# FingerPrint_Device_PCB.net
KiCad netlist of a schematic drawn in Altium Designer
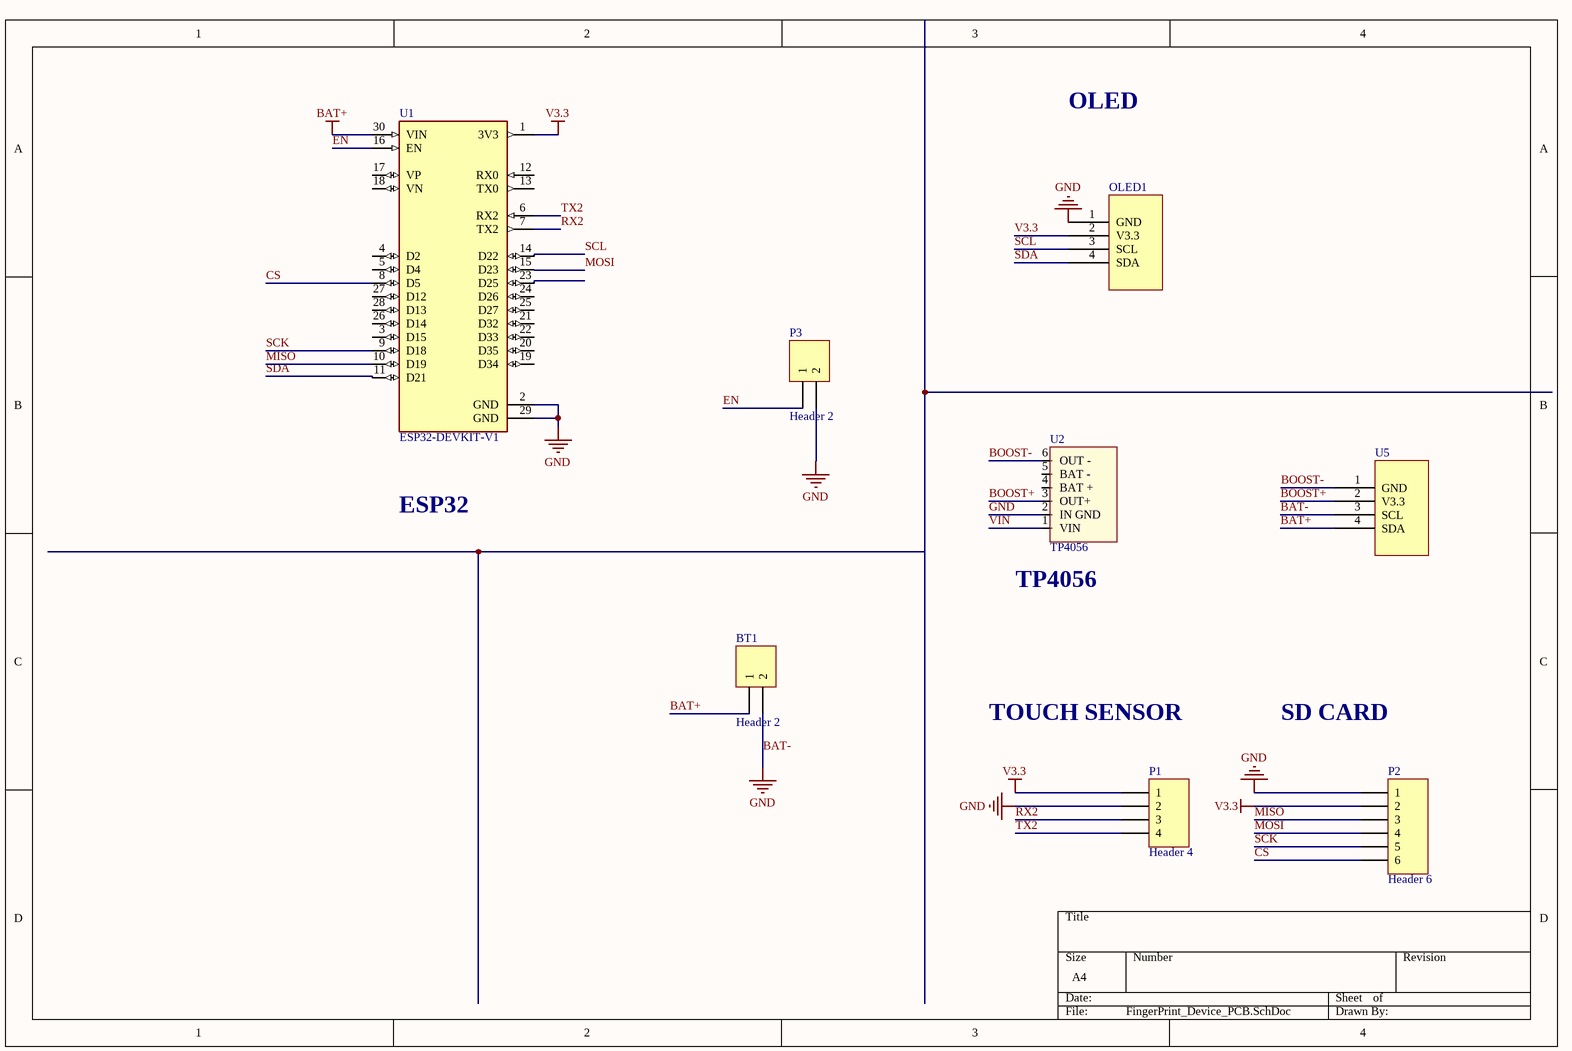
[diagram p0: FingerPrint_Device_PCB.SchDoc]

(export (version "E")
  (design (tool "Eeschema 10.0.6"))
  (components
    (comp (ref "BT1")
      (value "Header 2")
      (footprint "HDR1X2")
      (description "Header, 2-Pin")
      (fields (field (name "PUBLISHER") "Altium Limited"))
      (libsource (lib "Miscellaneous Connectors") (part "Header 2"))
    )
    (comp (ref "OLED1") (value "OLED") (footprint "OLED") (libsource (lib "OLED") (part "OLED")))
    (comp (ref "P1")
      (value "Header 4")
      (footprint "HDR1X4")
      (description "Header, 4-Pin")
      (fields (field (name "PUBLISHER") "Altium Limited"))
      (libsource (lib "Miscellaneous Connectors") (part "Header 4"))
    )
    (comp (ref "P2")
      (value "Header 6")
      (footprint "HDR1X6")
      (description "Header, 6-Pin")
      (fields (field (name "PUBLISHER") "Altium Limited"))
      (libsource (lib "Miscellaneous Connectors") (part "Header 6"))
    )
    (comp (ref "P3")
      (value "Header 2")
      (footprint "HDR1X2")
      (description "Header, 2-Pin")
      (fields (field (name "PUBLISHER") "Altium Limited"))
      (libsource (lib "Miscellaneous Connectors") (part "Header 2"))
    )
    (comp (ref "U1")
      (value "ESP32-DEVKIT-V1")
      (footprint "MODULE_ESP32_DEVKIT_V1")
      (fields (field (name "MF") "Do it"))
      (libsource (lib "ESP32-DEVKIT-V1") (part "ESP32-DEVKIT-V1"))
    )
    (comp (ref "U2")
      (value "TP4056")
      (footprint "tp4056")
      (description "Dushan")
      (libsource (lib "TP4056") (part "TP4056"))
    )
    (comp (ref "U5") (value "OLED") (footprint "MT3608") (libsource (lib "OLED") (part "OLED")))
  )
  (nets
    (net (code "1") (name "/BOOST+") (class "Default")
      (node (ref "U2") (pin "3") (pinfunction "OUT+_3") (pintype "passive"))
      (node (ref "U5") (pin "2") (pinfunction "V3.3_2") (pintype "passive"))
    )
    (net (code "2") (name "/BOOST-") (class "Default")
      (node (ref "U2") (pin "6") (pinfunction "OUT_-_6") (pintype "passive"))
      (node (ref "U5") (pin "1") (pinfunction "GND_1") (pintype "passive"))
    )
    (net (code "3") (name "/CS") (class "Default")
      (node (ref "P2") (pin "6") (pinfunction "6_6") (pintype "passive"))
      (node (ref "U1") (pin "8") (pinfunction "D5_8") (pintype "bidirectional"))
    )
    (net (code "4") (name "/EN") (class "Default")
      (node (ref "P3") (pin "1") (pinfunction "1_1") (pintype "passive"))
      (node (ref "U1") (pin "16") (pinfunction "EN_16") (pintype "input"))
    )
    (net (code "5") (name "/MISO") (class "Default")
      (node (ref "P2") (pin "3") (pinfunction "3_3") (pintype "passive"))
      (node (ref "U1") (pin "10") (pinfunction "D19_10") (pintype "bidirectional"))
    )
    (net (code "6") (name "/MOSI") (class "Default")
      (node (ref "P2") (pin "4") (pinfunction "4_4") (pintype "passive"))
      (node (ref "U1") (pin "15") (pinfunction "D23_15") (pintype "bidirectional"))
    )
    (net (code "7") (name "/RX2") (class "Default")
      (node (ref "P1") (pin "3") (pinfunction "3_3") (pintype "passive"))
      (node (ref "U1") (pin "7") (pinfunction "TX2_7") (pintype "output"))
    )
    (net (code "8") (name "/SCK") (class "Default")
      (node (ref "P2") (pin "5") (pinfunction "5_5") (pintype "passive"))
      (node (ref "U1") (pin "9") (pinfunction "D18_9") (pintype "bidirectional"))
    )
    (net (code "9") (name "/SCL") (class "Default")
      (node (ref "OLED1") (pin "3") (pinfunction "SCL_3") (pintype "passive"))
      (node (ref "U1") (pin "14") (pinfunction "D22_14") (pintype "bidirectional"))
    )
    (net (code "10") (name "/SDA") (class "Default")
      (node (ref "OLED1") (pin "4") (pinfunction "SDA_4") (pintype "passive"))
      (node (ref "U1") (pin "11") (pinfunction "D21_11") (pintype "bidirectional"))
    )
    (net (code "11") (name "/TX2") (class "Default")
      (node (ref "P1") (pin "4") (pinfunction "4_4") (pintype "passive"))
      (node (ref "U1") (pin "6") (pinfunction "RX2_6") (pintype "input"))
    )
    (net (code "12") (name "/VIN") (class "Default")
      (node (ref "U2") (pin "1") (pinfunction "VIN_1") (pintype "passive"))
    )
    (net (code "13") (name "BAT+") (class "Default")
      (node (ref "BT1") (pin "1") (pinfunction "1_1") (pintype "passive"))
      (node (ref "U1") (pin "30") (pinfunction "VIN_30") (pintype "input"))
      (node (ref "U5") (pin "4") (pinfunction "SDA_4") (pintype "passive"))
    )
    (net (code "14") (name "GND") (class "Default")
      (node (ref "BT1") (pin "2") (pinfunction "2_2") (pintype "passive"))
      (node (ref "OLED1") (pin "1") (pinfunction "GND_1") (pintype "passive"))
      (node (ref "P1") (pin "2") (pinfunction "2_2") (pintype "passive"))
      (node (ref "P2") (pin "1") (pinfunction "1_1") (pintype "passive"))
      (node (ref "P3") (pin "2") (pinfunction "2_2") (pintype "passive"))
      (node (ref "U1") (pin "2") (pinfunction "GND_2") (pintype "power_in"))
      (node (ref "U1") (pin "29") (pinfunction "GND_29") (pintype "power_in"))
      (node (ref "U2") (pin "2") (pinfunction "IN_GND_2") (pintype "passive"))
      (node (ref "U5") (pin "3") (pinfunction "SCL_3") (pintype "passive"))
    )
    (net (code "15") (name "V3.3") (class "Default")
      (node (ref "OLED1") (pin "2") (pinfunction "V3.3_2") (pintype "passive"))
      (node (ref "P1") (pin "1") (pinfunction "1_1") (pintype "passive"))
      (node (ref "P2") (pin "2") (pinfunction "2_2") (pintype "passive"))
      (node (ref "U1") (pin "1") (pinfunction "3V3_1") (pintype "output"))
    )
    (net (code "16") (name "unconnected-(U1-D2-Pad4)") (class "Default")
      (node (ref "U1") (pin "4") (pinfunction "D2_4") (pintype "bidirectional"))
    )
    (net (code "17") (name "unconnected-(U1-D4-Pad5)") (class "Default")
      (node (ref "U1") (pin "5") (pinfunction "D4_5") (pintype "bidirectional"))
    )
    (net (code "18") (name "unconnected-(U1-D12-Pad27)") (class "Default")
      (node (ref "U1") (pin "27") (pinfunction "D12_27") (pintype "bidirectional"))
    )
    (net (code "19") (name "unconnected-(U1-D13-Pad28)") (class "Default")
      (node (ref "U1") (pin "28") (pinfunction "D13_28") (pintype "bidirectional"))
    )
    (net (code "20") (name "unconnected-(U1-D14-Pad26)") (class "Default")
      (node (ref "U1") (pin "26") (pinfunction "D14_26") (pintype "bidirectional"))
    )
    (net (code "21") (name "unconnected-(U1-D15-Pad3)") (class "Default")
      (node (ref "U1") (pin "3") (pinfunction "D15_3") (pintype "bidirectional"))
    )
    (net (code "22") (name "unconnected-(U1-D25-Pad23)") (class "Default")
      (node (ref "U1") (pin "23") (pinfunction "D25_23") (pintype "bidirectional"))
    )
    (net (code "23") (name "unconnected-(U1-D26-Pad24)") (class "Default")
      (node (ref "U1") (pin "24") (pinfunction "D26_24") (pintype "bidirectional"))
    )
    (net (code "24") (name "unconnected-(U1-D27-Pad25)") (class "Default")
      (node (ref "U1") (pin "25") (pinfunction "D27_25") (pintype "bidirectional"))
    )
    (net (code "25") (name "unconnected-(U1-D32-Pad21)") (class "Default")
      (node (ref "U1") (pin "21") (pinfunction "D32_21") (pintype "bidirectional"))
    )
    (net (code "26") (name "unconnected-(U1-D33-Pad22)") (class "Default")
      (node (ref "U1") (pin "22") (pinfunction "D33_22") (pintype "bidirectional"))
    )
    (net (code "27") (name "unconnected-(U1-D34-Pad19)") (class "Default")
      (node (ref "U1") (pin "19") (pinfunction "D34_19") (pintype "bidirectional"))
    )
    (net (code "28") (name "unconnected-(U1-D35-Pad20)") (class "Default")
      (node (ref "U1") (pin "20") (pinfunction "D35_20") (pintype "bidirectional"))
    )
    (net (code "29") (name "unconnected-(U1-RX0-Pad12)") (class "Default")
      (node (ref "U1") (pin "12") (pinfunction "RX0_12") (pintype "input"))
    )
    (net (code "30") (name "unconnected-(U1-TX0-Pad13)") (class "Default")
      (node (ref "U1") (pin "13") (pinfunction "TX0_13") (pintype "output"))
    )
    (net (code "31") (name "unconnected-(U1-VN-Pad18)") (class "Default")
      (node (ref "U1") (pin "18") (pinfunction "VN_18") (pintype "bidirectional"))
    )
    (net (code "32") (name "unconnected-(U1-VP-Pad17)") (class "Default")
      (node (ref "U1") (pin "17") (pinfunction "VP_17") (pintype "bidirectional"))
    )
    (net (code "33") (name "unconnected-(U2-BAT_+-Pad4)") (class "Default")
      (node (ref "U2") (pin "4") (pinfunction "BAT_+_4") (pintype "passive"))
    )
    (net (code "34") (name "unconnected-(U2-BAT_--Pad5)") (class "Default")
      (node (ref "U2") (pin "5") (pinfunction "BAT_-_5") (pintype "passive"))
    )
  )
)
